# ALU_OR.net
KiCad netlist of a schematic drawn in Altium Designer
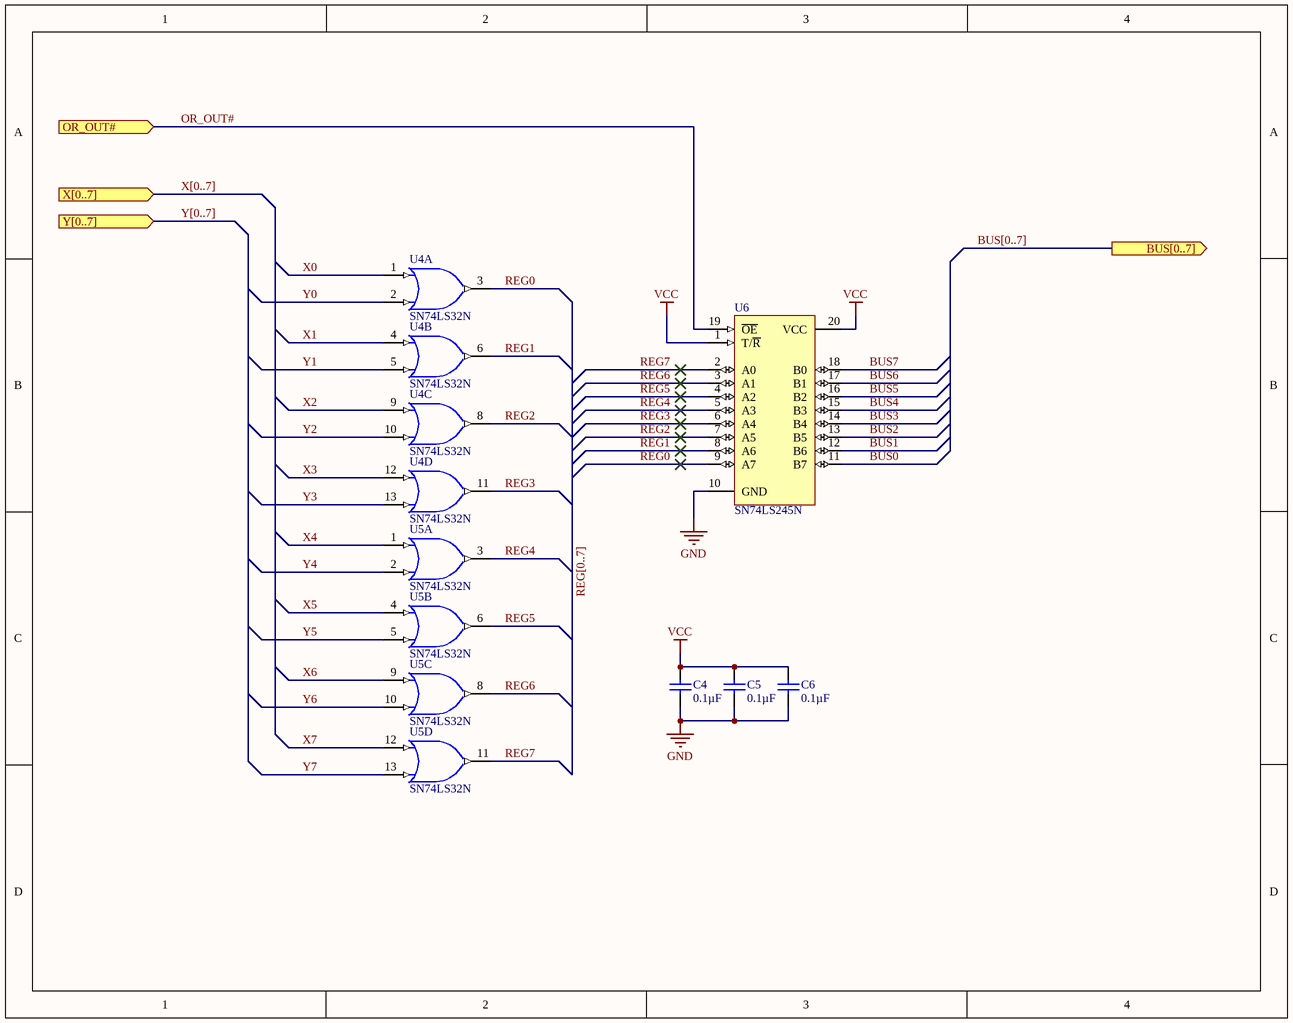
[diagram p0: ALU_OR.SchDoc]

(export (version "E")
  (design (tool "Eeschema 10.0.6"))
  (components
    (comp (ref "C4")
      (value "K104K15X7RF5TL2")
      (footprint "VISH-K104K15X7RF5TL2")
      (description "Ceramic Capacitor, 100 nF, +/- 10%, 50 V, -55 to 125 degC, 2-Pin THD, RoHS, Tape and Reel")
      (fields
        (field (name "MANUFACTURER") "Vishay")
        (field (name "TOLERANCE") "±10%")
        (field (name "CAPACITANCE") "0.1µF")
      )
      (libsource (lib "Altium Content Vault") (part "CAP-NP-2"))
    )
    (comp (ref "C5")
      (value "K104K15X7RF5TL2")
      (footprint "VISH-K104K15X7RF5TL2")
      (description "Ceramic Capacitor, 100 nF, +/- 10%, 50 V, -55 to 125 degC, 2-Pin THD, RoHS, Tape and Reel")
      (fields
        (field (name "MANUFACTURER") "Vishay")
        (field (name "TOLERANCE") "±10%")
        (field (name "CAPACITANCE") "0.1µF")
      )
      (libsource (lib "Altium Content Vault") (part "CAP-NP-2"))
    )
    (comp (ref "C6")
      (value "K104K15X7RF5TL2")
      (footprint "VISH-K104K15X7RF5TL2")
      (description "Ceramic Capacitor, 100 nF, +/- 10%, 50 V, -55 to 125 degC, 2-Pin THD, RoHS, Tape and Reel")
      (fields
        (field (name "MANUFACTURER") "Vishay")
        (field (name "TOLERANCE") "±10%")
        (field (name "CAPACITANCE") "0.1µF")
      )
      (libsource (lib "Altium Content Vault") (part "CAP-NP-2"))
    )
    (comp (ref "U4")
      (value "SN74LS32N")
      (footprint "N014")
      (description "Quadruple 2-Input Positive-OR Gate")
      (fields (field (name "PUBLISHER") "Altium Limited"))
      (libsource (lib "TI Logic Gate 2") (part "SN74LS32N"))
    )
    (comp (ref "U5")
      (value "SN74LS32N")
      (footprint "N014")
      (description "Quadruple 2-Input Positive-OR Gate")
      (fields (field (name "PUBLISHER") "Altium Limited"))
      (libsource (lib "TI Logic Gate 2") (part "SN74LS32N"))
    )
    (comp (ref "U6")
      (value "SN74LS245N")
      (footprint "N020")
      (description "Octal Bus Transceiver with 3-State Outputs")
      (fields (field (name "PUBLISHER") "Altium Limited"))
      (libsource (lib "TI Interface 8-Bit Line Transceiver") (part "SN74LS245N"))
    )
  )
  (nets
    (net (code "1") (name "/BUS0") (class "Default")
      (node (ref "U6") (pin "11") (pinfunction "B7_11") (pintype "bidirectional"))
    )
    (net (code "2") (name "/BUS1") (class "Default")
      (node (ref "U6") (pin "12") (pinfunction "B6_12") (pintype "bidirectional"))
    )
    (net (code "3") (name "/BUS2") (class "Default")
      (node (ref "U6") (pin "13") (pinfunction "B5_13") (pintype "bidirectional"))
    )
    (net (code "4") (name "/BUS3") (class "Default")
      (node (ref "U6") (pin "14") (pinfunction "B4_14") (pintype "bidirectional"))
    )
    (net (code "5") (name "/BUS4") (class "Default")
      (node (ref "U6") (pin "15") (pinfunction "B3_15") (pintype "bidirectional"))
    )
    (net (code "6") (name "/BUS5") (class "Default")
      (node (ref "U6") (pin "16") (pinfunction "B2_16") (pintype "bidirectional"))
    )
    (net (code "7") (name "/BUS6") (class "Default")
      (node (ref "U6") (pin "17") (pinfunction "B1_17") (pintype "bidirectional"))
    )
    (net (code "8") (name "/BUS7") (class "Default")
      (node (ref "U6") (pin "18") (pinfunction "B0_18") (pintype "bidirectional"))
    )
    (net (code "10") (name "/OR_OUT#") (class "Default")
      (node (ref "U6") (pin "19") (pinfunction "~{OE}_19") (pintype "input"))
    )
    (net (code "11") (name "/REG0") (class "Default")
      (node (ref "U4") (pin "3") (pinfunction "Y_3") (pintype "output"))
      (node (ref "U6") (pin "9") (pinfunction "A7_9") (pintype "bidirectional"))
    )
    (net (code "12") (name "/REG1") (class "Default")
      (node (ref "U4") (pin "6") (pinfunction "Y_6") (pintype "output"))
      (node (ref "U6") (pin "8") (pinfunction "A6_8") (pintype "bidirectional"))
    )
    (net (code "13") (name "/REG2") (class "Default")
      (node (ref "U4") (pin "8") (pinfunction "Y_8") (pintype "output"))
      (node (ref "U6") (pin "7") (pinfunction "A5_7") (pintype "bidirectional"))
    )
    (net (code "14") (name "/REG3") (class "Default")
      (node (ref "U4") (pin "11") (pinfunction "Y_11") (pintype "output"))
      (node (ref "U6") (pin "6") (pinfunction "A4_6") (pintype "bidirectional"))
    )
    (net (code "15") (name "/REG4") (class "Default")
      (node (ref "U5") (pin "3") (pinfunction "Y_3") (pintype "output"))
      (node (ref "U6") (pin "5") (pinfunction "A3_5") (pintype "bidirectional"))
    )
    (net (code "16") (name "/REG5") (class "Default")
      (node (ref "U5") (pin "6") (pinfunction "Y_6") (pintype "output"))
      (node (ref "U6") (pin "4") (pinfunction "A2_4") (pintype "bidirectional"))
    )
    (net (code "17") (name "/REG6") (class "Default")
      (node (ref "U5") (pin "8") (pinfunction "Y_8") (pintype "output"))
      (node (ref "U6") (pin "3") (pinfunction "A1_3") (pintype "bidirectional"))
    )
    (net (code "18") (name "/REG7") (class "Default")
      (node (ref "U5") (pin "11") (pinfunction "Y_11") (pintype "output"))
      (node (ref "U6") (pin "2") (pinfunction "A0_2") (pintype "bidirectional"))
    )
    (net (code "20") (name "/X0") (class "Default")
      (node (ref "U4") (pin "1") (pinfunction "A_1") (pintype "input"))
    )
    (net (code "21") (name "/X1") (class "Default")
      (node (ref "U4") (pin "4") (pinfunction "A_4") (pintype "input"))
    )
    (net (code "22") (name "/X2") (class "Default")
      (node (ref "U4") (pin "9") (pinfunction "A_9") (pintype "input"))
    )
    (net (code "23") (name "/X3") (class "Default")
      (node (ref "U4") (pin "12") (pinfunction "A_12") (pintype "input"))
    )
    (net (code "24") (name "/X4") (class "Default")
      (node (ref "U5") (pin "1") (pinfunction "A_1") (pintype "input"))
    )
    (net (code "25") (name "/X5") (class "Default")
      (node (ref "U5") (pin "4") (pinfunction "A_4") (pintype "input"))
    )
    (net (code "26") (name "/X6") (class "Default")
      (node (ref "U5") (pin "9") (pinfunction "A_9") (pintype "input"))
    )
    (net (code "27") (name "/X7") (class "Default")
      (node (ref "U5") (pin "12") (pinfunction "A_12") (pintype "input"))
    )
    (net (code "29") (name "/Y0") (class "Default")
      (node (ref "U4") (pin "2") (pinfunction "B_2") (pintype "input"))
    )
    (net (code "30") (name "/Y1") (class "Default")
      (node (ref "U4") (pin "5") (pinfunction "B_5") (pintype "input"))
    )
    (net (code "31") (name "/Y2") (class "Default")
      (node (ref "U4") (pin "10") (pinfunction "B_10") (pintype "input"))
    )
    (net (code "32") (name "/Y3") (class "Default")
      (node (ref "U4") (pin "13") (pinfunction "B_13") (pintype "input"))
    )
    (net (code "33") (name "/Y4") (class "Default")
      (node (ref "U5") (pin "2") (pinfunction "B_2") (pintype "input"))
    )
    (net (code "34") (name "/Y5") (class "Default")
      (node (ref "U5") (pin "5") (pinfunction "B_5") (pintype "input"))
    )
    (net (code "35") (name "/Y6") (class "Default")
      (node (ref "U5") (pin "10") (pinfunction "B_10") (pintype "input"))
    )
    (net (code "36") (name "/Y7") (class "Default")
      (node (ref "U5") (pin "13") (pinfunction "B_13") (pintype "input"))
    )
    (net (code "38") (name "GND") (class "Default")
      (node (ref "C4") (pin "2") (pinfunction "2_2") (pintype "passive"))
      (node (ref "C5") (pin "2") (pinfunction "2_2") (pintype "passive"))
      (node (ref "C6") (pin "2") (pinfunction "2_2") (pintype "passive"))
      (node (ref "U4") (pin "7") (pinfunction "GND_7") (pintype "power_in"))
      (node (ref "U5") (pin "7") (pinfunction "GND_7") (pintype "power_in"))
      (node (ref "U6") (pin "10") (pinfunction "GND_10") (pintype "power_in"))
    )
    (net (code "39") (name "VCC") (class "Default")
      (node (ref "C4") (pin "1") (pinfunction "1_1") (pintype "passive"))
      (node (ref "C5") (pin "1") (pinfunction "1_1") (pintype "passive"))
      (node (ref "C6") (pin "1") (pinfunction "1_1") (pintype "passive"))
      (node (ref "U4") (pin "14") (pinfunction "VCC_14") (pintype "power_in"))
      (node (ref "U5") (pin "14") (pinfunction "VCC_14") (pintype "power_in"))
      (node (ref "U6") (pin "1") (pinfunction "T/~{R}_1") (pintype "input"))
      (node (ref "U6") (pin "20") (pinfunction "VCC_20") (pintype "power_in"))
    )
  )
)
